# BRAMPS.net
KiCad netlist of a schematic drawn in EAGLE
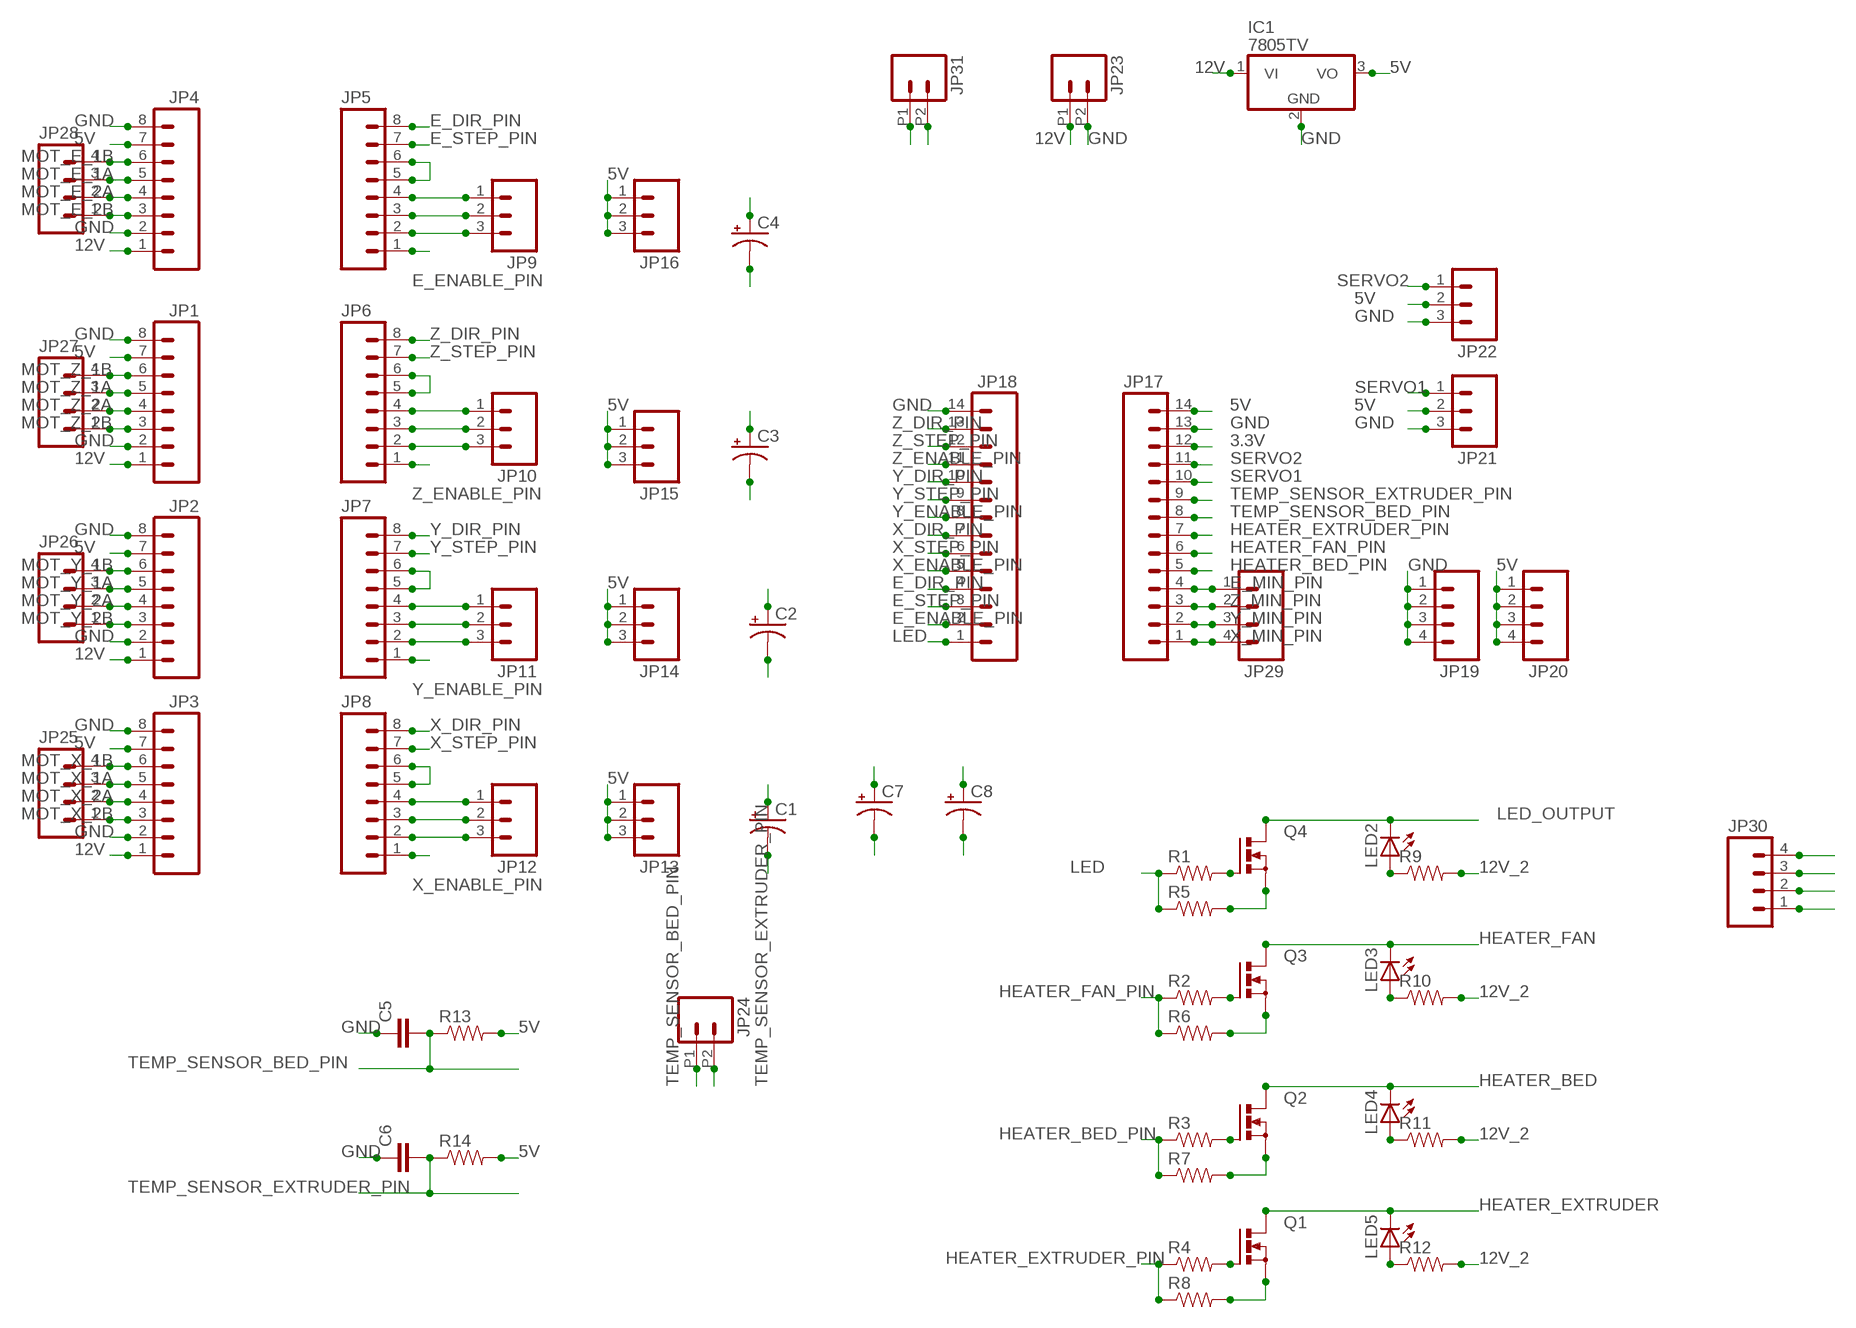
[diagram p0: schematic, sheet 1]

(export (version "E")
  (design (tool "Eeschema 10.0.6"))
  (components
    (comp (ref "C1")
      (value "CAP_POLPTH2")
      (footprint "eagle-import:CPOL-RADIAL-10UF-25V")
      (libsource (lib "eagle-import") (part "CAP_POLPTH2"))
    )
    (comp (ref "C2")
      (value "CAP_POLPTH2")
      (footprint "eagle-import:CPOL-RADIAL-10UF-25V")
      (libsource (lib "eagle-import") (part "CAP_POLPTH2"))
    )
    (comp (ref "C3")
      (value "CAP_POLPTH2")
      (footprint "eagle-import:CPOL-RADIAL-10UF-25V")
      (libsource (lib "eagle-import") (part "CAP_POLPTH2"))
    )
    (comp (ref "C4")
      (value "CAP_POLPTH2")
      (footprint "eagle-import:CPOL-RADIAL-10UF-25V")
      (libsource (lib "eagle-import") (part "CAP_POLPTH2"))
    )
    (comp (ref "C5")
      (value "CAP0805")
      (footprint "eagle-import:0805")
      (libsource (lib "eagle-import") (part "CAP0805"))
    )
    (comp (ref "C6")
      (value "CAP0805")
      (footprint "eagle-import:0805")
      (libsource (lib "eagle-import") (part "CAP0805"))
    )
    (comp (ref "C7")
      (value "CAP_POLPTH2")
      (footprint "eagle-import:CPOL-RADIAL-10UF-25V")
      (libsource (lib "eagle-import") (part "CAP_POLPTH2"))
    )
    (comp (ref "C8")
      (value "CAP_POLPTH2")
      (footprint "eagle-import:CPOL-RADIAL-10UF-25V")
      (libsource (lib "eagle-import") (part "CAP_POLPTH2"))
    )
    (comp (ref "IC1")
      (value "7805TV")
      (footprint "eagle-import:TO220V")
      (libsource (lib "eagle-import") (part "78TV05"))
    )
    (comp (ref "JP1")
      (value "M08NO_SILK_FEMALE_PTH")
      (footprint "eagle-import:1X08_NO_SILK")
      (libsource (lib "eagle-import") (part "M08NO_SILK_FEMALE_PTH"))
    )
    (comp (ref "JP2")
      (value "M08NO_SILK_FEMALE_PTH")
      (footprint "eagle-import:1X08_NO_SILK")
      (libsource (lib "eagle-import") (part "M08NO_SILK_FEMALE_PTH"))
    )
    (comp (ref "JP3")
      (value "M08NO_SILK_FEMALE_PTH")
      (footprint "eagle-import:1X08_NO_SILK")
      (libsource (lib "eagle-import") (part "M08NO_SILK_FEMALE_PTH"))
    )
    (comp (ref "JP4")
      (value "M08NO_SILK_FEMALE_PTH")
      (footprint "eagle-import:1X08_NO_SILK")
      (libsource (lib "eagle-import") (part "M08NO_SILK_FEMALE_PTH"))
    )
    (comp (ref "JP5")
      (value "M08NO_SILK_FEMALE_PTH")
      (footprint "eagle-import:1X08_NO_SILK")
      (libsource (lib "eagle-import") (part "M08NO_SILK_FEMALE_PTH"))
    )
    (comp (ref "JP6")
      (value "M08NO_SILK_FEMALE_PTH")
      (footprint "eagle-import:1X08_NO_SILK")
      (libsource (lib "eagle-import") (part "M08NO_SILK_FEMALE_PTH"))
    )
    (comp (ref "JP7")
      (value "M08NO_SILK_FEMALE_PTH")
      (footprint "eagle-import:1X08_NO_SILK")
      (libsource (lib "eagle-import") (part "M08NO_SILK_FEMALE_PTH"))
    )
    (comp (ref "JP8")
      (value "M08NO_SILK_FEMALE_PTH")
      (footprint "eagle-import:1X08_NO_SILK")
      (libsource (lib "eagle-import") (part "M08NO_SILK_FEMALE_PTH"))
    )
    (comp (ref "JP9")
      (value "M03PTH")
      (footprint "eagle-import:1X03")
      (libsource (lib "eagle-import") (part "M03PTH"))
    )
    (comp (ref "JP10")
      (value "M03PTH")
      (footprint "eagle-import:1X03")
      (libsource (lib "eagle-import") (part "M03PTH"))
    )
    (comp (ref "JP11")
      (value "M03PTH")
      (footprint "eagle-import:1X03")
      (libsource (lib "eagle-import") (part "M03PTH"))
    )
    (comp (ref "JP12")
      (value "M03PTH")
      (footprint "eagle-import:1X03")
      (libsource (lib "eagle-import") (part "M03PTH"))
    )
    (comp (ref "JP13")
      (value "M03PTH")
      (footprint "eagle-import:1X03")
      (libsource (lib "eagle-import") (part "M03PTH"))
    )
    (comp (ref "JP14")
      (value "M03PTH")
      (footprint "eagle-import:1X03")
      (libsource (lib "eagle-import") (part "M03PTH"))
    )
    (comp (ref "JP15")
      (value "M03PTH")
      (footprint "eagle-import:1X03")
      (libsource (lib "eagle-import") (part "M03PTH"))
    )
    (comp (ref "JP16")
      (value "M03PTH")
      (footprint "eagle-import:1X03")
      (libsource (lib "eagle-import") (part "M03PTH"))
    )
    (comp (ref "JP17")
      (value "M14")
      (footprint "eagle-import:1X14")
      (libsource (lib "eagle-import") (part "M14"))
    )
    (comp (ref "JP18")
      (value "M14")
      (footprint "eagle-import:1X14")
      (libsource (lib "eagle-import") (part "M14"))
    )
    (comp (ref "JP19")
      (value "M04NO_SILK_ALL_ROUND")
      (footprint "eagle-import:1X04_NO_SILK_ALL_ROUND")
      (libsource (lib "eagle-import") (part "M04NO_SILK_ALL_ROUND"))
    )
    (comp (ref "JP20")
      (value "M04NO_SILK_ALL_ROUND")
      (footprint "eagle-import:1X04_NO_SILK_ALL_ROUND")
      (libsource (lib "eagle-import") (part "M04NO_SILK_ALL_ROUND"))
    )
    (comp (ref "JP21")
      (value "M03PTH")
      (footprint "eagle-import:1X03")
      (libsource (lib "eagle-import") (part "M03PTH"))
    )
    (comp (ref "JP22")
      (value "M03PTH")
      (footprint "eagle-import:1X03")
      (libsource (lib "eagle-import") (part "M03PTH"))
    )
    (comp (ref "JP23")
      (value "M022.54MM_SCREWTERM")
      (footprint "eagle-import:1X02_2.54_SCREWTERM")
      (libsource (lib "eagle-import") (part "M022.54MM_SCREWTERM"))
    )
    (comp (ref "JP24")
      (value "M022.54MM_SCREWTERM")
      (footprint "eagle-import:1X02_2.54_SCREWTERM")
      (libsource (lib "eagle-import") (part "M022.54MM_SCREWTERM"))
    )
    (comp (ref "JP25")
      (value "M04SCREW")
      (footprint "eagle-import:SCREWTERMINAL-3.5MM-4")
      (libsource (lib "eagle-import") (part "M04SCREW"))
    )
    (comp (ref "JP26")
      (value "M04SCREW")
      (footprint "eagle-import:SCREWTERMINAL-3.5MM-4")
      (libsource (lib "eagle-import") (part "M04SCREW"))
    )
    (comp (ref "JP27")
      (value "M04SCREW")
      (footprint "eagle-import:SCREWTERMINAL-3.5MM-4")
      (libsource (lib "eagle-import") (part "M04SCREW"))
    )
    (comp (ref "JP28")
      (value "M04SCREW")
      (footprint "eagle-import:SCREWTERMINAL-3.5MM-4")
      (libsource (lib "eagle-import") (part "M04SCREW"))
    )
    (comp (ref "JP29")
      (value "M04NO_SILK_ALL_ROUND")
      (footprint "eagle-import:1X04_NO_SILK_ALL_ROUND")
      (libsource (lib "eagle-import") (part "M04NO_SILK_ALL_ROUND"))
    )
    (comp (ref "JP30")
      (value "M04SCREW")
      (footprint "eagle-import:SCREWTERMINAL-3.5MM-4")
      (libsource (lib "eagle-import") (part "M04SCREW"))
    )
    (comp (ref "JP31")
      (value "M022.54MM_SCREWTERM")
      (footprint "eagle-import:1X02_2.54_SCREWTERM")
      (libsource (lib "eagle-import") (part "M022.54MM_SCREWTERM"))
    )
    (comp (ref "LED2")
      (value "LEDCHIP-LED0805")
      (footprint "eagle-import:CHIP-LED0805")
      (libsource (lib "eagle-import") (part "LEDCHIP-LED0805"))
    )
    (comp (ref "LED3")
      (value "LEDCHIP-LED0805")
      (footprint "eagle-import:CHIP-LED0805")
      (libsource (lib "eagle-import") (part "LEDCHIP-LED0805"))
    )
    (comp (ref "LED4")
      (value "LEDCHIP-LED0805")
      (footprint "eagle-import:CHIP-LED0805")
      (libsource (lib "eagle-import") (part "LEDCHIP-LED0805"))
    )
    (comp (ref "LED5")
      (value "LEDCHIP-LED0805")
      (footprint "eagle-import:CHIP-LED0805")
      (libsource (lib "eagle-import") (part "LEDCHIP-LED0805"))
    )
    (comp (ref "Q1")
      (value "PMOSFET_NTO220BV")
      (footprint "eagle-import:TO220BV")
      (libsource (lib "eagle-import") (part "PMOSFET_NTO220BV"))
    )
    (comp (ref "Q2")
      (value "PMOSFET_NTO220BV")
      (footprint "eagle-import:TO220BV")
      (libsource (lib "eagle-import") (part "PMOSFET_NTO220BV"))
    )
    (comp (ref "Q3")
      (value "PMOSFET_NTO220BV")
      (footprint "eagle-import:TO220BV")
      (libsource (lib "eagle-import") (part "PMOSFET_NTO220BV"))
    )
    (comp (ref "Q4")
      (value "PMOSFET_NTO220BV")
      (footprint "eagle-import:TO220BV")
      (libsource (lib "eagle-import") (part "PMOSFET_NTO220BV"))
    )
    (comp (ref "R1")
      (value "RESISTOR0805-RES")
      (footprint "eagle-import:0805")
      (libsource (lib "eagle-import") (part "RESISTOR0805-RES"))
    )
    (comp (ref "R2")
      (value "RESISTOR0805-RES")
      (footprint "eagle-import:0805")
      (libsource (lib "eagle-import") (part "RESISTOR0805-RES"))
    )
    (comp (ref "R3")
      (value "RESISTOR0805-RES")
      (footprint "eagle-import:0805")
      (libsource (lib "eagle-import") (part "RESISTOR0805-RES"))
    )
    (comp (ref "R4")
      (value "RESISTOR0805-RES")
      (footprint "eagle-import:0805")
      (libsource (lib "eagle-import") (part "RESISTOR0805-RES"))
    )
    (comp (ref "R5")
      (value "RESISTOR0805-RES")
      (footprint "eagle-import:0805")
      (libsource (lib "eagle-import") (part "RESISTOR0805-RES"))
    )
    (comp (ref "R6")
      (value "RESISTOR0805-RES")
      (footprint "eagle-import:0805")
      (libsource (lib "eagle-import") (part "RESISTOR0805-RES"))
    )
    (comp (ref "R7")
      (value "RESISTOR0805-RES")
      (footprint "eagle-import:0805")
      (libsource (lib "eagle-import") (part "RESISTOR0805-RES"))
    )
    (comp (ref "R8")
      (value "RESISTOR0805-RES")
      (footprint "eagle-import:0805")
      (libsource (lib "eagle-import") (part "RESISTOR0805-RES"))
    )
    (comp (ref "R9")
      (value "RESISTOR0805-RES")
      (footprint "eagle-import:0805")
      (libsource (lib "eagle-import") (part "RESISTOR0805-RES"))
    )
    (comp (ref "R10")
      (value "RESISTOR0805-RES")
      (footprint "eagle-import:0805")
      (libsource (lib "eagle-import") (part "RESISTOR0805-RES"))
    )
    (comp (ref "R11")
      (value "RESISTOR0805-RES")
      (footprint "eagle-import:0805")
      (libsource (lib "eagle-import") (part "RESISTOR0805-RES"))
    )
    (comp (ref "R12")
      (value "RESISTOR0805-RES")
      (footprint "eagle-import:0805")
      (libsource (lib "eagle-import") (part "RESISTOR0805-RES"))
    )
    (comp (ref "R13")
      (value "RESISTOR0805-RES")
      (footprint "eagle-import:0805")
      (libsource (lib "eagle-import") (part "RESISTOR0805-RES"))
    )
    (comp (ref "R14")
      (value "RESISTOR0805-RES")
      (footprint "eagle-import:0805")
      (libsource (lib "eagle-import") (part "RESISTOR0805-RES"))
    )
  )
  (nets
    (net (code "1") (name "/3.3V") (class "Default")
      (node (ref "JP17") (pin "12") (pinfunction "12_12") (pintype "passive"))
    )
    (net (code "2") (name "/5V") (class "Default")
      (node (ref "C8") (pin "1") (pinfunction "+_1") (pintype "passive"))
      (node (ref "IC1") (pin "3") (pinfunction "VO_3") (pintype "passive"))
      (node (ref "JP1") (pin "7") (pinfunction "7_7") (pintype "passive"))
      (node (ref "JP13") (pin "1") (pinfunction "1_1") (pintype "passive"))
      (node (ref "JP13") (pin "2") (pinfunction "2_2") (pintype "passive"))
      (node (ref "JP13") (pin "3") (pinfunction "3_3") (pintype "passive"))
      (node (ref "JP14") (pin "1") (pinfunction "1_1") (pintype "passive"))
      (node (ref "JP14") (pin "2") (pinfunction "2_2") (pintype "passive"))
      (node (ref "JP14") (pin "3") (pinfunction "3_3") (pintype "passive"))
      (node (ref "JP15") (pin "1") (pinfunction "1_1") (pintype "passive"))
      (node (ref "JP15") (pin "2") (pinfunction "2_2") (pintype "passive"))
      (node (ref "JP15") (pin "3") (pinfunction "3_3") (pintype "passive"))
      (node (ref "JP16") (pin "1") (pinfunction "1_1") (pintype "passive"))
      (node (ref "JP16") (pin "2") (pinfunction "2_2") (pintype "passive"))
      (node (ref "JP16") (pin "3") (pinfunction "3_3") (pintype "passive"))
      (node (ref "JP17") (pin "14") (pinfunction "14_14") (pintype "passive"))
      (node (ref "JP2") (pin "7") (pinfunction "7_7") (pintype "passive"))
      (node (ref "JP20") (pin "1") (pinfunction "1_1") (pintype "passive"))
      (node (ref "JP20") (pin "2") (pinfunction "2_2") (pintype "passive"))
      (node (ref "JP20") (pin "3") (pinfunction "3_3") (pintype "passive"))
      (node (ref "JP20") (pin "4") (pinfunction "4_4") (pintype "passive"))
      (node (ref "JP21") (pin "2") (pinfunction "2_2") (pintype "passive"))
      (node (ref "JP22") (pin "2") (pinfunction "2_2") (pintype "passive"))
      (node (ref "JP3") (pin "7") (pinfunction "7_7") (pintype "passive"))
      (node (ref "JP4") (pin "7") (pinfunction "7_7") (pintype "passive"))
      (node (ref "R13") (pin "2") (pinfunction "2_2") (pintype "passive"))
      (node (ref "R14") (pin "2") (pinfunction "2_2") (pintype "passive"))
    )
    (net (code "3") (name "/12V") (class "Default")
      (node (ref "C1") (pin "1") (pinfunction "+_1") (pintype "passive"))
      (node (ref "C2") (pin "1") (pinfunction "+_1") (pintype "passive"))
      (node (ref "C3") (pin "1") (pinfunction "+_1") (pintype "passive"))
      (node (ref "C4") (pin "1") (pinfunction "+_1") (pintype "passive"))
      (node (ref "C7") (pin "1") (pinfunction "+_1") (pintype "passive"))
      (node (ref "IC1") (pin "1") (pinfunction "VI_1") (pintype "input"))
      (node (ref "JP1") (pin "1") (pinfunction "1_1") (pintype "passive"))
      (node (ref "JP2") (pin "1") (pinfunction "1_1") (pintype "passive"))
      (node (ref "JP23") (pin "P1") (pinfunction "1_P1") (pintype "passive"))
      (node (ref "JP3") (pin "1") (pinfunction "1_1") (pintype "passive"))
      (node (ref "JP4") (pin "1") (pinfunction "1_1") (pintype "passive"))
    )
    (net (code "4") (name "/12V_2") (class "Default")
      (node (ref "JP31") (pin "P1") (pinfunction "1_P1") (pintype "passive"))
      (node (ref "R10") (pin "2") (pinfunction "2_2") (pintype "passive"))
      (node (ref "R11") (pin "2") (pinfunction "2_2") (pintype "passive"))
      (node (ref "R12") (pin "2") (pinfunction "2_2") (pintype "passive"))
      (node (ref "R9") (pin "2") (pinfunction "2_2") (pintype "passive"))
    )
    (net (code "5") (name "/E_DIR_PIN") (class "Default")
      (node (ref "JP18") (pin "4") (pinfunction "4_4") (pintype "passive"))
      (node (ref "JP5") (pin "8") (pinfunction "8_8") (pintype "passive"))
    )
    (net (code "6") (name "/E_ENABLE_PIN") (class "Default")
      (node (ref "JP18") (pin "2") (pinfunction "2_2") (pintype "passive"))
      (node (ref "JP5") (pin "1") (pinfunction "1_1") (pintype "passive"))
    )
    (net (code "7") (name "/E_MIN_PIN") (class "Default")
      (node (ref "JP17") (pin "4") (pinfunction "4_4") (pintype "passive"))
      (node (ref "JP29") (pin "1") (pinfunction "1_1") (pintype "passive"))
    )
    (net (code "8") (name "/E_STEP_PIN") (class "Default")
      (node (ref "JP18") (pin "3") (pinfunction "3_3") (pintype "passive"))
      (node (ref "JP5") (pin "7") (pinfunction "7_7") (pintype "passive"))
    )
    (net (code "9") (name "/GND") (class "Default")
      (node (ref "C1") (pin "2") (pinfunction "-_2") (pintype "passive"))
      (node (ref "C2") (pin "2") (pinfunction "-_2") (pintype "passive"))
      (node (ref "C3") (pin "2") (pinfunction "-_2") (pintype "passive"))
      (node (ref "C4") (pin "2") (pinfunction "-_2") (pintype "passive"))
      (node (ref "C5") (pin "1") (pinfunction "1_1") (pintype "passive"))
      (node (ref "C6") (pin "1") (pinfunction "1_1") (pintype "passive"))
      (node (ref "C7") (pin "2") (pinfunction "-_2") (pintype "passive"))
      (node (ref "C8") (pin "2") (pinfunction "-_2") (pintype "passive"))
      (node (ref "IC1") (pin "2") (pinfunction "GND_2") (pintype "passive"))
      (node (ref "JP1") (pin "2") (pinfunction "2_2") (pintype "passive"))
      (node (ref "JP1") (pin "8") (pinfunction "8_8") (pintype "passive"))
      (node (ref "JP17") (pin "13") (pinfunction "13_13") (pintype "passive"))
      (node (ref "JP18") (pin "14") (pinfunction "14_14") (pintype "passive"))
      (node (ref "JP19") (pin "1") (pinfunction "1_1") (pintype "passive"))
      (node (ref "JP19") (pin "2") (pinfunction "2_2") (pintype "passive"))
      (node (ref "JP19") (pin "3") (pinfunction "3_3") (pintype "passive"))
      (node (ref "JP19") (pin "4") (pinfunction "4_4") (pintype "passive"))
      (node (ref "JP2") (pin "2") (pinfunction "2_2") (pintype "passive"))
      (node (ref "JP2") (pin "8") (pinfunction "8_8") (pintype "passive"))
      (node (ref "JP21") (pin "3") (pinfunction "3_3") (pintype "passive"))
      (node (ref "JP22") (pin "3") (pinfunction "3_3") (pintype "passive"))
      (node (ref "JP23") (pin "P2") (pinfunction "2_P2") (pintype "passive"))
      (node (ref "JP3") (pin "2") (pinfunction "2_2") (pintype "passive"))
      (node (ref "JP3") (pin "8") (pinfunction "8_8") (pintype "passive"))
      (node (ref "JP4") (pin "2") (pinfunction "2_2") (pintype "passive"))
      (node (ref "JP4") (pin "8") (pinfunction "8_8") (pintype "passive"))
      (node (ref "Q1") (pin "S") (pinfunction "S_S") (pintype "passive"))
      (node (ref "Q2") (pin "S") (pinfunction "S_S") (pintype "passive"))
      (node (ref "Q3") (pin "S") (pinfunction "S_S") (pintype "passive"))
      (node (ref "Q4") (pin "S") (pinfunction "S_S") (pintype "passive"))
      (node (ref "R5") (pin "2") (pinfunction "2_2") (pintype "passive"))
      (node (ref "R6") (pin "2") (pinfunction "2_2") (pintype "passive"))
      (node (ref "R7") (pin "2") (pinfunction "2_2") (pintype "passive"))
      (node (ref "R8") (pin "2") (pinfunction "2_2") (pintype "passive"))
    )
    (net (code "10") (name "/HEATER_BED") (class "Default")
      (node (ref "JP30") (pin "3") (pinfunction "3_3") (pintype "passive"))
      (node (ref "LED4") (pin "C") (pinfunction "C_C") (pintype "passive"))
      (node (ref "Q2") (pin "D") (pinfunction "D_D") (pintype "passive"))
    )
    (net (code "11") (name "/HEATER_BED_PIN") (class "Default")
      (node (ref "JP17") (pin "5") (pinfunction "5_5") (pintype "passive"))
      (node (ref "R3") (pin "1") (pinfunction "1_1") (pintype "passive"))
      (node (ref "R7") (pin "1") (pinfunction "1_1") (pintype "passive"))
    )
    (net (code "12") (name "/HEATER_EXTRUDER") (class "Default")
      (node (ref "JP30") (pin "1") (pinfunction "1_1") (pintype "passive"))
      (node (ref "LED5") (pin "C") (pinfunction "C_C") (pintype "passive"))
      (node (ref "Q1") (pin "D") (pinfunction "D_D") (pintype "passive"))
    )
    (net (code "13") (name "/HEATER_EXTRUDER_PIN") (class "Default")
      (node (ref "JP17") (pin "7") (pinfunction "7_7") (pintype "passive"))
      (node (ref "R4") (pin "1") (pinfunction "1_1") (pintype "passive"))
      (node (ref "R8") (pin "1") (pinfunction "1_1") (pintype "passive"))
    )
    (net (code "14") (name "/HEATER_FAN") (class "Default")
      (node (ref "JP30") (pin "2") (pinfunction "2_2") (pintype "passive"))
      (node (ref "LED3") (pin "C") (pinfunction "C_C") (pintype "passive"))
      (node (ref "Q3") (pin "D") (pinfunction "D_D") (pintype "passive"))
    )
    (net (code "15") (name "/HEATER_FAN_PIN") (class "Default")
      (node (ref "JP17") (pin "6") (pinfunction "6_6") (pintype "passive"))
      (node (ref "R2") (pin "1") (pinfunction "1_1") (pintype "passive"))
      (node (ref "R6") (pin "1") (pinfunction "1_1") (pintype "passive"))
    )
    (net (code "16") (name "/LED") (class "Default")
      (node (ref "JP18") (pin "1") (pinfunction "1_1") (pintype "passive"))
      (node (ref "R1") (pin "1") (pinfunction "1_1") (pintype "passive"))
      (node (ref "R5") (pin "1") (pinfunction "1_1") (pintype "passive"))
    )
    (net (code "17") (name "/LED_OUTPUT") (class "Default")
      (node (ref "JP30") (pin "4") (pinfunction "4_4") (pintype "passive"))
      (node (ref "LED2") (pin "C") (pinfunction "C_C") (pintype "passive"))
      (node (ref "Q4") (pin "D") (pinfunction "D_D") (pintype "passive"))
    )
    (net (code "18") (name "/MOT_E_1A") (class "Default")
      (node (ref "JP28") (pin "3") (pinfunction "3_3") (pintype "passive"))
      (node (ref "JP4") (pin "5") (pinfunction "5_5") (pintype "passive"))
    )
    (net (code "19") (name "/MOT_E_1B") (class "Default")
      (node (ref "JP28") (pin "4") (pinfunction "4_4") (pintype "passive"))
      (node (ref "JP4") (pin "6") (pinfunction "6_6") (pintype "passive"))
    )
    (net (code "20") (name "/MOT_E_2A") (class "Default")
      (node (ref "JP28") (pin "2") (pinfunction "2_2") (pintype "passive"))
      (node (ref "JP4") (pin "4") (pinfunction "4_4") (pintype "passive"))
    )
    (net (code "21") (name "/MOT_E_2B") (class "Default")
      (node (ref "JP28") (pin "1") (pinfunction "1_1") (pintype "passive"))
      (node (ref "JP4") (pin "3") (pinfunction "3_3") (pintype "passive"))
    )
    (net (code "22") (name "/MOT_X_1A") (class "Default")
      (node (ref "JP25") (pin "3") (pinfunction "3_3") (pintype "passive"))
      (node (ref "JP3") (pin "5") (pinfunction "5_5") (pintype "passive"))
    )
    (net (code "23") (name "/MOT_X_1B") (class "Default")
      (node (ref "JP25") (pin "4") (pinfunction "4_4") (pintype "passive"))
      (node (ref "JP3") (pin "6") (pinfunction "6_6") (pintype "passive"))
    )
    (net (code "24") (name "/MOT_X_2A") (class "Default")
      (node (ref "JP25") (pin "2") (pinfunction "2_2") (pintype "passive"))
      (node (ref "JP3") (pin "4") (pinfunction "4_4") (pintype "passive"))
    )
    (net (code "25") (name "/MOT_X_2B") (class "Default")
      (node (ref "JP25") (pin "1") (pinfunction "1_1") (pintype "passive"))
      (node (ref "JP3") (pin "3") (pinfunction "3_3") (pintype "passive"))
    )
    (net (code "26") (name "/MOT_Y_1A") (class "Default")
      (node (ref "JP2") (pin "5") (pinfunction "5_5") (pintype "passive"))
      (node (ref "JP26") (pin "3") (pinfunction "3_3") (pintype "passive"))
    )
    (net (code "27") (name "/MOT_Y_1B") (class "Default")
      (node (ref "JP2") (pin "6") (pinfunction "6_6") (pintype "passive"))
      (node (ref "JP26") (pin "4") (pinfunction "4_4") (pintype "passive"))
    )
    (net (code "28") (name "/MOT_Y_2A") (class "Default")
      (node (ref "JP2") (pin "4") (pinfunction "4_4") (pintype "passive"))
      (node (ref "JP26") (pin "2") (pinfunction "2_2") (pintype "passive"))
    )
    (net (code "29") (name "/MOT_Y_2B") (class "Default")
      (node (ref "JP2") (pin "3") (pinfunction "3_3") (pintype "passive"))
      (node (ref "JP26") (pin "1") (pinfunction "1_1") (pintype "passive"))
    )
    (net (code "30") (name "/MOT_Z_1A") (class "Default")
      (node (ref "JP1") (pin "5") (pinfunction "5_5") (pintype "passive"))
      (node (ref "JP27") (pin "3") (pinfunction "3_3") (pintype "passive"))
    )
    (net (code "31") (name "/MOT_Z_1B") (class "Default")
      (node (ref "JP1") (pin "6") (pinfunction "6_6") (pintype "passive"))
      (node (ref "JP27") (pin "4") (pinfunction "4_4") (pintype "passive"))
    )
    (net (code "32") (name "/MOT_Z_2A") (class "Default")
      (node (ref "JP1") (pin "4") (pinfunction "4_4") (pintype "passive"))
      (node (ref "JP27") (pin "2") (pinfunction "2_2") (pintype "passive"))
    )
    (net (code "33") (name "/MOT_Z_2B") (class "Default")
      (node (ref "JP1") (pin "3") (pinfunction "3_3") (pintype "passive"))
      (node (ref "JP27") (pin "1") (pinfunction "1_1") (pintype "passive"))
    )
    (net (code "34") (name "/SERVO1") (class "Default")
      (node (ref "JP17") (pin "10") (pinfunction "10_10") (pintype "passive"))
      (node (ref "JP21") (pin "1") (pinfunction "1_1") (pintype "passive"))
    )
    (net (code "35") (name "/SERVO2") (class "Default")
      (node (ref "JP17") (pin "11") (pinfunction "11_11") (pintype "passive"))
      (node (ref "JP22") (pin "1") (pinfunction "1_1") (pintype "passive"))
    )
    (net (code "36") (name "/TEMP_SENSOR_BED_PIN") (class "Default")
      (node (ref "C5") (pin "2") (pinfunction "2_2") (pintype "passive"))
      (node (ref "JP17") (pin "8") (pinfunction "8_8") (pintype "passive"))
      (node (ref "JP24") (pin "P1") (pinfunction "1_P1") (pintype "passive"))
      (node (ref "R13") (pin "1") (pinfunction "1_1") (pintype "passive"))
    )
    (net (code "37") (name "/TEMP_SENSOR_EXTRUDER_PIN") (class "Default")
      (node (ref "C6") (pin "2") (pinfunction "2_2") (pintype "passive"))
      (node (ref "JP17") (pin "9") (pinfunction "9_9") (pintype "passive"))
      (node (ref "JP24") (pin "P2") (pinfunction "2_P2") (pintype "passive"))
      (node (ref "R14") (pin "1") (pinfunction "1_1") (pintype "passive"))
    )
    (net (code "38") (name "/X_DIR_PIN") (class "Default")
      (node (ref "JP18") (pin "7") (pinfunction "7_7") (pintype "passive"))
      (node (ref "JP8") (pin "8") (pinfunction "8_8") (pintype "passive"))
    )
    (net (code "39") (name "/X_ENABLE_PIN") (class "Default")
      (node (ref "JP18") (pin "5") (pinfunction "5_5") (pintype "passive"))
      (node (ref "JP8") (pin "1") (pinfunction "1_1") (pintype "passive"))
    )
    (net (code "40") (name "/X_MIN_PIN") (class "Default")
      (node (ref "JP17") (pin "1") (pinfunction "1_1") (pintype "passive"))
      (node (ref "JP29") (pin "4") (pinfunction "4_4") (pintype "passive"))
    )
    (net (code "41") (name "/X_STEP_PIN") (class "Default")
      (node (ref "JP18") (pin "6") (pinfunction "6_6") (pintype "passive"))
      (node (ref "JP8") (pin "7") (pinfunction "7_7") (pintype "passive"))
    )
    (net (code "42") (name "/Y_DIR_PIN") (class "Default")
      (node (ref "JP18") (pin "10") (pinfunction "10_10") (pintype "passive"))
      (node (ref "JP7") (pin "8") (pinfunction "8_8") (pintype "passive"))
    )
    (net (code "43") (name "/Y_ENABLE_PIN") (class "Default")
      (node (ref "JP18") (pin "8") (pinfunction "8_8") (pintype "passive"))
      (node (ref "JP7") (pin "1") (pinfunction "1_1") (pintype "passive"))
    )
    (net (code "44") (name "/Y_MIN_PIN") (class "Default")
      (node (ref "JP17") (pin "2") (pinfunction "2_2") (pintype "passive"))
      (node (ref "JP29") (pin "3") (pinfunction "3_3") (pintype "passive"))
    )
    (net (code "45") (name "/Y_STEP_PIN") (class "Default")
      (node (ref "JP18") (pin "9") (pinfunction "9_9") (pintype "passive"))
      (node (ref "JP7") (pin "7") (pinfunction "7_7") (pintype "passive"))
    )
    (net (code "46") (name "/Z_DIR_PIN") (class "Default")
      (node (ref "JP18") (pin "13") (pinfunction "13_13") (pintype "passive"))
      (node (ref "JP6") (pin "8") (pinfunction "8_8") (pintype "passive"))
    )
    (net (code "47") (name "/Z_ENABLE_PIN") (class "Default")
      (node (ref "JP18") (pin "11") (pinfunction "11_11") (pintype "passive"))
      (node (ref "JP6") (pin "1") (pinfunction "1_1") (pintype "passive"))
    )
    (net (code "48") (name "/Z_MIN_PIN") (class "Default")
      (node (ref "JP17") (pin "3") (pinfunction "3_3") (pintype "passive"))
      (node (ref "JP29") (pin "2") (pinfunction "2_2") (pintype "passive"))
    )
    (net (code "49") (name "/Z_STEP_PIN") (class "Default")
      (node (ref "JP18") (pin "12") (pinfunction "12_12") (pintype "passive"))
      (node (ref "JP6") (pin "7") (pinfunction "7_7") (pintype "passive"))
    )
    (net (code "50") (name "Net-(JP5-Pad2)") (class "Default")
      (node (ref "JP5") (pin "2") (pinfunction "2_2") (pintype "passive"))
      (node (ref "JP9") (pin "3") (pinfunction "3_3") (pintype "passive"))
    )
    (net (code "51") (name "Net-(JP5-Pad3)") (class "Default")
      (node (ref "JP5") (pin "3") (pinfunction "3_3") (pintype "passive"))
      (node (ref "JP9") (pin "2") (pinfunction "2_2") (pintype "passive"))
    )
    (net (code "52") (name "Net-(JP5-Pad4)") (class "Default")
      (node (ref "JP5") (pin "4") (pinfunction "4_4") (pintype "passive"))
      (node (ref "JP9") (pin "1") (pinfunction "1_1") (pintype "passive"))
    )
    (net (code "53") (name "Net-(JP5-Pad5)") (class "Default")
      (node (ref "JP5") (pin "5") (pinfunction "5_5") (pintype "passive"))
      (node (ref "JP5") (pin "6") (pinfunction "6_6") (pintype "passive"))
    )
    (net (code "54") (name "Net-(JP6-Pad5)") (class "Default")
      (node (ref "JP6") (pin "5") (pinfunction "5_5") (pintype "passive"))
      (node (ref "JP6") (pin "6") (pinfunction "6_6") (pintype "passive"))
    )
    (net (code "55") (name "Net-(JP7-Pad5)") (class "Default")
      (node (ref "JP7") (pin "5") (pinfunction "5_5") (pintype "passive"))
      (node (ref "JP7") (pin "6") (pinfunction "6_6") (pintype "passive"))
    )
    (net (code "56") (name "Net-(JP8-Pad5)") (class "Default")
      (node (ref "JP8") (pin "5") (pinfunction "5_5") (pintype "passive"))
      (node (ref "JP8") (pin "6") (pinfunction "6_6") (pintype "passive"))
    )
    (net (code "57") (name "Net-(JP10-Pad1)") (class "Default")
      (node (ref "JP10") (pin "1") (pinfunction "1_1") (pintype "passive"))
      (node (ref "JP6") (pin "4") (pinfunction "4_4") (pintype "passive"))
    )
    (net (code "58") (name "Net-(JP10-Pad2)") (class "Default")
      (node (ref "JP10") (pin "2") (pinfunction "2_2") (pintype "passive"))
      (node (ref "JP6") (pin "3") (pinfunction "3_3") (pintype "passive"))
    )
    (net (code "59") (name "Net-(JP10-Pad3)") (class "Default")
      (node (ref "JP10") (pin "3") (pinfunction "3_3") (pintype "passive"))
      (node (ref "JP6") (pin "2") (pinfunction "2_2") (pintype "passive"))
    )
    (net (code "60") (name "Net-(JP11-Pad1)") (class "Default")
      (node (ref "JP11") (pin "1") (pinfunction "1_1") (pintype "passive"))
      (node (ref "JP7") (pin "4") (pinfunction "4_4") (pintype "passive"))
    )
    (net (code "61") (name "Net-(JP11-Pad2)") (class "Default")
      (node (ref "JP11") (pin "2") (pinfunction "2_2") (pintype "passive"))
      (node (ref "JP7") (pin "3") (pinfunction "3_3") (pintype "passive"))
    )
    (net (code "62") (name "Net-(JP11-Pad3)") (class "Default")
      (node (ref "JP11") (pin "3") (pinfunction "3_3") (pintype "passive"))
      (node (ref "JP7") (pin "2") (pinfunction "2_2") (pintype "passive"))
    )
    (net (code "63") (name "Net-(JP12-Pad1)") (class "Default")
      (node (ref "JP12") (pin "1") (pinfunction "1_1") (pintype "passive"))
      (node (ref "JP8") (pin "4") (pinfunction "4_4") (pintype "passive"))
    )
    (net (code "64") (name "Net-(JP12-Pad2)") (class "Default")
      (node (ref "JP12") (pin "2") (pinfunction "2_2") (pintype "passive"))
      (node (ref "JP8") (pin "3") (pinfunction "3_3") (pintype "passive"))
    )
    (net (code "65") (name "Net-(JP12-Pad3)") (class "Default")
      (node (ref "JP12") (pin "3") (pinfunction "3_3") (pintype "passive"))
      (node (ref "JP8") (pin "2") (pinfunction "2_2") (pintype "passive"))
    )
    (net (code "66") (name "Net-(LED2-PadA)") (class "Default")
      (node (ref "LED2") (pin "A") (pinfunction "A_A") (pintype "passive"))
      (node (ref "R9") (pin "1") (pinfunction "1_1") (pintype "passive"))
    )
    (net (code "67") (name "Net-(LED3-PadA)") (class "Default")
      (node (ref "LED3") (pin "A") (pinfunction "A_A") (pintype "passive"))
      (node (ref "R10") (pin "1") (pinfunction "1_1") (pintype "passive"))
    )
    (net (code "68") (name "Net-(LED4-PadA)") (class "Default")
      (node (ref "LED4") (pin "A") (pinfunction "A_A") (pintype "passive"))
      (node (ref "R11") (pin "1") (pinfunction "1_1") (pintype "passive"))
    )
    (net (code "69") (name "Net-(LED5-PadA)") (class "Default")
      (node (ref "LED5") (pin "A") (pinfunction "A_A") (pintype "passive"))
      (node (ref "R12") (pin "1") (pinfunction "1_1") (pintype "passive"))
    )
    (net (code "70") (name "Net-(Q1-PadG)") (class "Default")
      (node (ref "Q1") (pin "G") (pinfunction "G_G") (pintype "passive"))
      (node (ref "R4") (pin "2") (pinfunction "2_2") (pintype "passive"))
    )
    (net (code "71") (name "Net-(Q2-PadG)") (class "Default")
      (node (ref "Q2") (pin "G") (pinfunction "G_G") (pintype "passive"))
      (node (ref "R3") (pin "2") (pinfunction "2_2") (pintype "passive"))
    )
    (net (code "72") (name "Net-(Q3-PadG)") (class "Default")
      (node (ref "Q3") (pin "G") (pinfunction "G_G") (pintype "passive"))
      (node (ref "R2") (pin "2") (pinfunction "2_2") (pintype "passive"))
    )
    (net (code "73") (name "Net-(Q4-PadG)") (class "Default")
      (node (ref "Q4") (pin "G") (pinfunction "G_G") (pintype "passive"))
      (node (ref "R1") (pin "2") (pinfunction "2_2") (pintype "passive"))
    )
    (net (code "74") (name "unconnected-(JP31-2-PadP2)") (class "Default")
      (node (ref "JP31") (pin "P2") (pinfunction "2_P2") (pintype "passive"))
    )
  )
)
